# RecvWeather.net
KiCad netlist of a schematic drawn in EAGLE
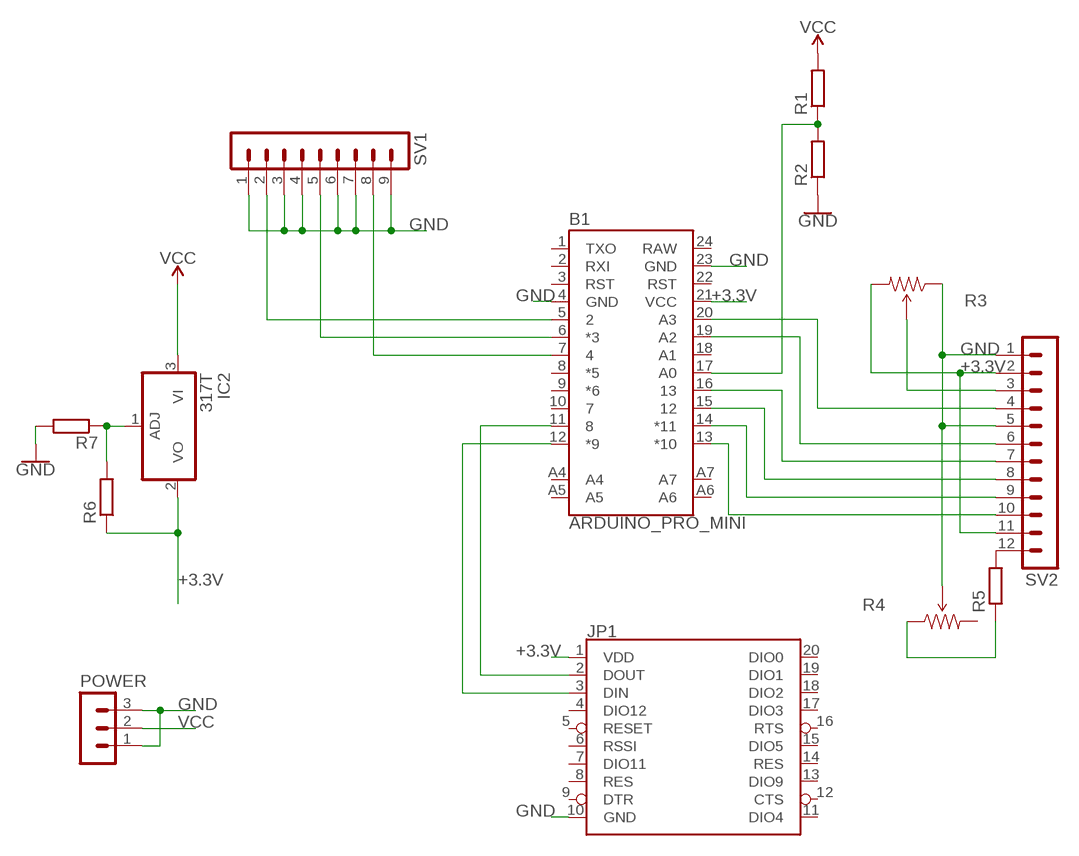
[diagram p0: schematic, sheet 1]

(export (version "E")
  (design (tool "Eeschema 10.0.6"))
  (components
    (comp (ref "B1")
      (value "ARDUINO_PRO_MINI")
      (footprint "eagle-import:ARDUINO_PRO_MINI")
      (libsource (lib "eagle-import") (part "ARDUINO_PRO_MINI"))
    )
    (comp (ref "IC2")
      (value "317T")
      (footprint "eagle-import:TO220H")
      (libsource (lib "eagle-import") (part "317T"))
    )
    (comp (ref "JP1")
      (value "XBEE")
      (footprint "eagle-import:XBEE")
      (libsource (lib "eagle-import") (part "XBEE"))
    )
    (comp (ref "POWER")
      (value "MA03-1")
      (footprint "eagle-import:MA03-1")
      (libsource (lib "eagle-import") (part "MA03-1"))
    )
    (comp (ref "R1")
      (value "R-EU_0309/12")
      (footprint "eagle-import:0309_12")
      (libsource (lib "eagle-import") (part "R-EU_0309/12"))
    )
    (comp (ref "R2")
      (value "R-EU_0309/12")
      (footprint "eagle-import:0309_12")
      (libsource (lib "eagle-import") (part "R-EU_0309/12"))
    )
    (comp (ref "R3")
      (value "TRIMPOTPTH")
      (footprint "eagle-import:TRIM_POT_PTH")
      (libsource (lib "eagle-import") (part "TRIMPOTPTH"))
    )
    (comp (ref "R4")
      (value "TRIMPOTPTH")
      (footprint "eagle-import:TRIM_POT_PTH")
      (libsource (lib "eagle-import") (part "TRIMPOTPTH"))
    )
    (comp (ref "R5")
      (value "R-EU_0309/12")
      (footprint "eagle-import:0309_12")
      (libsource (lib "eagle-import") (part "R-EU_0309/12"))
    )
    (comp (ref "R6")
      (value "R-EU_0309/12")
      (footprint "eagle-import:0309_12")
      (libsource (lib "eagle-import") (part "R-EU_0309/12"))
    )
    (comp (ref "R7")
      (value "R-EU_0309/12")
      (footprint "eagle-import:0309_12")
      (libsource (lib "eagle-import") (part "R-EU_0309/12"))
    )
    (comp (ref "SV1")
      (value "MA09-1")
      (footprint "eagle-import:MA09-1")
      (libsource (lib "eagle-import") (part "MA09-1"))
    )
    (comp (ref "SV2")
      (value "MA12-1")
      (footprint "eagle-import:MA12-1")
      (libsource (lib "eagle-import") (part "MA12-1"))
    )
  )
  (nets
    (net (code "1") (name "/+3.3V") (class "Default")
      (node (ref "B1") (pin "21") (pinfunction "VCC_21") (pintype "power_in"))
      (node (ref "IC2") (pin "2") (pinfunction "VO_2") (pintype "passive"))
      (node (ref "JP1") (pin "1") (pinfunction "VDD_1") (pintype "power_in"))
      (node (ref "R3") (pin "3") (pinfunction "CW_3") (pintype "passive"))
      (node (ref "R6") (pin "1") (pinfunction "1_1") (pintype "passive"))
      (node (ref "SV2") (pin "11") (pinfunction "11_11") (pintype "passive"))
      (node (ref "SV2") (pin "2") (pinfunction "2_2") (pintype "passive"))
    )
    (net (code "2") (name "/RAW") (class "Default")
      (node (ref "B1") (pin "24") (pinfunction "RAW_24") (pintype "power_in"))
    )
    (net (code "3") (name "GND") (class "Default")
      (node (ref "B1") (pin "23") (pinfunction "GND_23") (pintype "power_in"))
      (node (ref "B1") (pin "4") (pinfunction "GND_4") (pintype "power_in"))
      (node (ref "JP1") (pin "10") (pinfunction "GND_10") (pintype "power_in"))
      (node (ref "POWER") (pin "1") (pinfunction "1_1") (pintype "passive"))
      (node (ref "POWER") (pin "3") (pinfunction "3_3") (pintype "passive"))
      (node (ref "R2") (pin "1") (pinfunction "1_1") (pintype "passive"))
      (node (ref "R3") (pin "1") (pinfunction "CCW_1") (pintype "passive"))
      (node (ref "R4") (pin "2") (pinfunction "WIPER_2") (pintype "passive"))
      (node (ref "R7") (pin "2") (pinfunction "2_2") (pintype "passive"))
      (node (ref "SV1") (pin "1") (pinfunction "1_1") (pintype "passive"))
      (node (ref "SV1") (pin "3") (pinfunction "3_3") (pintype "passive"))
      (node (ref "SV1") (pin "4") (pinfunction "4_4") (pintype "passive"))
      (node (ref "SV1") (pin "6") (pinfunction "6_6") (pintype "passive"))
      (node (ref "SV1") (pin "7") (pinfunction "7_7") (pintype "passive"))
      (node (ref "SV1") (pin "9") (pinfunction "9_9") (pintype "passive"))
      (node (ref "SV2") (pin "1") (pinfunction "1_1") (pintype "passive"))
      (node (ref "SV2") (pin "5") (pinfunction "5_5") (pintype "passive"))
    )
    (net (code "4") (name "Net-(B1-*3)") (class "Default")
      (node (ref "B1") (pin "6") (pinfunction "*3_6") (pintype "bidirectional"))
      (node (ref "SV1") (pin "5") (pinfunction "5_5") (pintype "passive"))
    )
    (net (code "5") (name "Net-(B1-*9)") (class "Default")
      (node (ref "B1") (pin "12") (pinfunction "*9_12") (pintype "bidirectional"))
      (node (ref "JP1") (pin "3") (pinfunction "DIN_3") (pintype "input"))
    )
    (net (code "6") (name "Net-(B1-*10)") (class "Default")
      (node (ref "B1") (pin "13") (pinfunction "*10_13") (pintype "bidirectional"))
      (node (ref "SV2") (pin "10") (pinfunction "10_10") (pintype "passive"))
    )
    (net (code "7") (name "Net-(B1-*11)") (class "Default")
      (node (ref "B1") (pin "14") (pinfunction "*11_14") (pintype "bidirectional"))
      (node (ref "SV2") (pin "9") (pinfunction "9_9") (pintype "passive"))
    )
    (net (code "8") (name "Net-(B1-2)") (class "Default")
      (node (ref "B1") (pin "5") (pinfunction "2_5") (pintype "bidirectional"))
      (node (ref "SV1") (pin "2") (pinfunction "2_2") (pintype "passive"))
    )
    (net (code "9") (name "Net-(B1-4)") (class "Default")
      (node (ref "B1") (pin "7") (pinfunction "4_7") (pintype "bidirectional"))
      (node (ref "SV1") (pin "8") (pinfunction "8_8") (pintype "passive"))
    )
    (net (code "10") (name "Net-(B1-8)") (class "Default")
      (node (ref "B1") (pin "11") (pinfunction "8_11") (pintype "bidirectional"))
      (node (ref "JP1") (pin "2") (pinfunction "DOUT_2") (pintype "output"))
    )
    (net (code "11") (name "Net-(B1-12)") (class "Default")
      (node (ref "B1") (pin "15") (pinfunction "12_15") (pintype "bidirectional"))
      (node (ref "SV2") (pin "8") (pinfunction "8_8") (pintype "passive"))
    )
    (net (code "12") (name "Net-(B1-13)") (class "Default")
      (node (ref "B1") (pin "16") (pinfunction "13_16") (pintype "bidirectional"))
      (node (ref "SV2") (pin "7") (pinfunction "7_7") (pintype "passive"))
    )
    (net (code "13") (name "Net-(B1-A0)") (class "Default")
      (node (ref "B1") (pin "17") (pinfunction "A0_17") (pintype "bidirectional"))
      (node (ref "R1") (pin "1") (pinfunction "1_1") (pintype "passive"))
      (node (ref "R2") (pin "2") (pinfunction "2_2") (pintype "passive"))
    )
    (net (code "14") (name "Net-(B1-A2)") (class "Default")
      (node (ref "B1") (pin "19") (pinfunction "A2_19") (pintype "bidirectional"))
      (node (ref "SV2") (pin "6") (pinfunction "6_6") (pintype "passive"))
    )
    (net (code "15") (name "Net-(B1-A3)") (class "Default")
      (node (ref "B1") (pin "20") (pinfunction "A3_20") (pintype "bidirectional"))
      (node (ref "SV2") (pin "4") (pinfunction "4_4") (pintype "passive"))
    )
    (net (code "16") (name "Net-(IC2-ADJ)") (class "Default")
      (node (ref "IC2") (pin "1") (pinfunction "ADJ_1") (pintype "input"))
      (node (ref "R6") (pin "2") (pinfunction "2_2") (pintype "passive"))
      (node (ref "R7") (pin "1") (pinfunction "1_1") (pintype "passive"))
    )
    (net (code "17") (name "Net-(R3-WIPER)") (class "Default")
      (node (ref "R3") (pin "2") (pinfunction "WIPER_2") (pintype "passive"))
      (node (ref "SV2") (pin "3") (pinfunction "3_3") (pintype "passive"))
    )
    (net (code "18") (name "Net-(R4-CCW)") (class "Default")
      (node (ref "R4") (pin "1") (pinfunction "CCW_1") (pintype "passive"))
      (node (ref "R5") (pin "1") (pinfunction "1_1") (pintype "passive"))
    )
    (net (code "19") (name "Net-(R5-Pad2)") (class "Default")
      (node (ref "R5") (pin "2") (pinfunction "2_2") (pintype "passive"))
      (node (ref "SV2") (pin "12") (pinfunction "12_12") (pintype "passive"))
    )
    (net (code "20") (name "VCC") (class "Default")
      (node (ref "IC2") (pin "3") (pinfunction "VI_3") (pintype "input"))
      (node (ref "POWER") (pin "2") (pinfunction "2_2") (pintype "passive"))
      (node (ref "R1") (pin "2") (pinfunction "2_2") (pintype "passive"))
    )
    (net (code "21") (name "unconnected-(B1-*5-Pad8)") (class "Default")
      (node (ref "B1") (pin "8") (pinfunction "*5_8") (pintype "bidirectional"))
    )
    (net (code "22") (name "unconnected-(B1-*6-Pad9)") (class "Default")
      (node (ref "B1") (pin "9") (pinfunction "*6_9") (pintype "bidirectional"))
    )
    (net (code "23") (name "unconnected-(B1-7-Pad10)") (class "Default")
      (node (ref "B1") (pin "10") (pinfunction "7_10") (pintype "bidirectional"))
    )
    (net (code "24") (name "unconnected-(B1-A1-Pad18)") (class "Default")
      (node (ref "B1") (pin "18") (pinfunction "A1_18") (pintype "bidirectional"))
    )
    (net (code "25") (name "unconnected-(B1-PadA4)") (class "Default")
      (node (ref "B1") (pin "A4") (pinfunction "A4_A4") (pintype "bidirectional"))
    )
    (net (code "26") (name "unconnected-(B1-PadA5)") (class "Default")
      (node (ref "B1") (pin "A5") (pinfunction "A5_A5") (pintype "bidirectional"))
    )
    (net (code "27") (name "unconnected-(B1-PadA6)") (class "Default")
      (node (ref "B1") (pin "A6") (pinfunction "A6_A6") (pintype "bidirectional"))
    )
    (net (code "28") (name "unconnected-(B1-PadA7)") (class "Default")
      (node (ref "B1") (pin "A7") (pinfunction "A7_A7") (pintype "bidirectional"))
    )
    (net (code "29") (name "unconnected-(B1-RST-Pad3)") (class "Default")
      (node (ref "B1") (pin "3") (pinfunction "RST_3") (pintype "bidirectional"))
    )
    (net (code "30") (name "unconnected-(B1-RST-Pad22)") (class "Default")
      (node (ref "B1") (pin "22") (pinfunction "RST_22") (pintype "bidirectional"))
    )
    (net (code "31") (name "unconnected-(B1-RXI-Pad2)") (class "Default")
      (node (ref "B1") (pin "2") (pinfunction "RXI_2") (pintype "bidirectional"))
    )
    (net (code "32") (name "unconnected-(B1-TXO-Pad1)") (class "Default")
      (node (ref "B1") (pin "1") (pinfunction "TXO_1") (pintype "bidirectional"))
    )
    (net (code "33") (name "unconnected-(JP1-CTS-Pad12)") (class "Default")
      (node (ref "JP1") (pin "12") (pinfunction "CTS_12") (pintype "output"))
    )
    (net (code "34") (name "unconnected-(JP1-DIO0-Pad20)") (class "Default")
      (node (ref "JP1") (pin "20") (pinfunction "DIO0_20") (pintype "bidirectional"))
    )
    (net (code "35") (name "unconnected-(JP1-DIO1-Pad19)") (class "Default")
      (node (ref "JP1") (pin "19") (pinfunction "DIO1_19") (pintype "bidirectional"))
    )
    (net (code "36") (name "unconnected-(JP1-DIO2-Pad18)") (class "Default")
      (node (ref "JP1") (pin "18") (pinfunction "DIO2_18") (pintype "bidirectional"))
    )
    (net (code "37") (name "unconnected-(JP1-DIO3-Pad17)") (class "Default")
      (node (ref "JP1") (pin "17") (pinfunction "DIO3_17") (pintype "bidirectional"))
    )
    (net (code "38") (name "unconnected-(JP1-DIO4-Pad11)") (class "Default")
      (node (ref "JP1") (pin "11") (pinfunction "DIO4_11") (pintype "bidirectional"))
    )
    (net (code "39") (name "unconnected-(JP1-DIO5-Pad15)") (class "Default")
      (node (ref "JP1") (pin "15") (pinfunction "DIO5_15") (pintype "bidirectional"))
    )
    (net (code "40") (name "unconnected-(JP1-DIO9-Pad13)") (class "Default")
      (node (ref "JP1") (pin "13") (pinfunction "DIO9_13") (pintype "bidirectional"))
    )
    (net (code "41") (name "unconnected-(JP1-DIO11-Pad7)") (class "Default")
      (node (ref "JP1") (pin "7") (pinfunction "DIO11_7") (pintype "bidirectional"))
    )
    (net (code "42") (name "unconnected-(JP1-DIO12-Pad4)") (class "Default")
      (node (ref "JP1") (pin "4") (pinfunction "DIO12_4") (pintype "bidirectional"))
    )
    (net (code "43") (name "unconnected-(JP1-DTR-Pad9)") (class "Default")
      (node (ref "JP1") (pin "9") (pinfunction "DTR_9") (pintype "bidirectional"))
    )
    (net (code "44") (name "unconnected-(JP1-RES-Pad8)") (class "Default")
      (node (ref "JP1") (pin "8") (pinfunction "RES_8") (pintype "bidirectional"))
    )
    (net (code "45") (name "unconnected-(JP1-RES-Pad14)") (class "Default")
      (node (ref "JP1") (pin "14") (pinfunction "RES_14") (pintype "bidirectional"))
    )
    (net (code "46") (name "unconnected-(JP1-RESET-Pad5)") (class "Default")
      (node (ref "JP1") (pin "5") (pinfunction "RESET_5") (pintype "input"))
    )
    (net (code "47") (name "unconnected-(JP1-RSSI-Pad6)") (class "Default")
      (node (ref "JP1") (pin "6") (pinfunction "RSSI_6") (pintype "bidirectional"))
    )
    (net (code "48") (name "unconnected-(JP1-RTS-Pad16)") (class "Default")
      (node (ref "JP1") (pin "16") (pinfunction "RTS_16") (pintype "input"))
    )
    (net (code "49") (name "unconnected-(R4-CW-Pad3)") (class "Default")
      (node (ref "R4") (pin "3") (pinfunction "CW_3") (pintype "passive"))
    )
  )
)
